# SWD_OptoIsolator.net
KiCad netlist of a schematic drawn in EAGLE
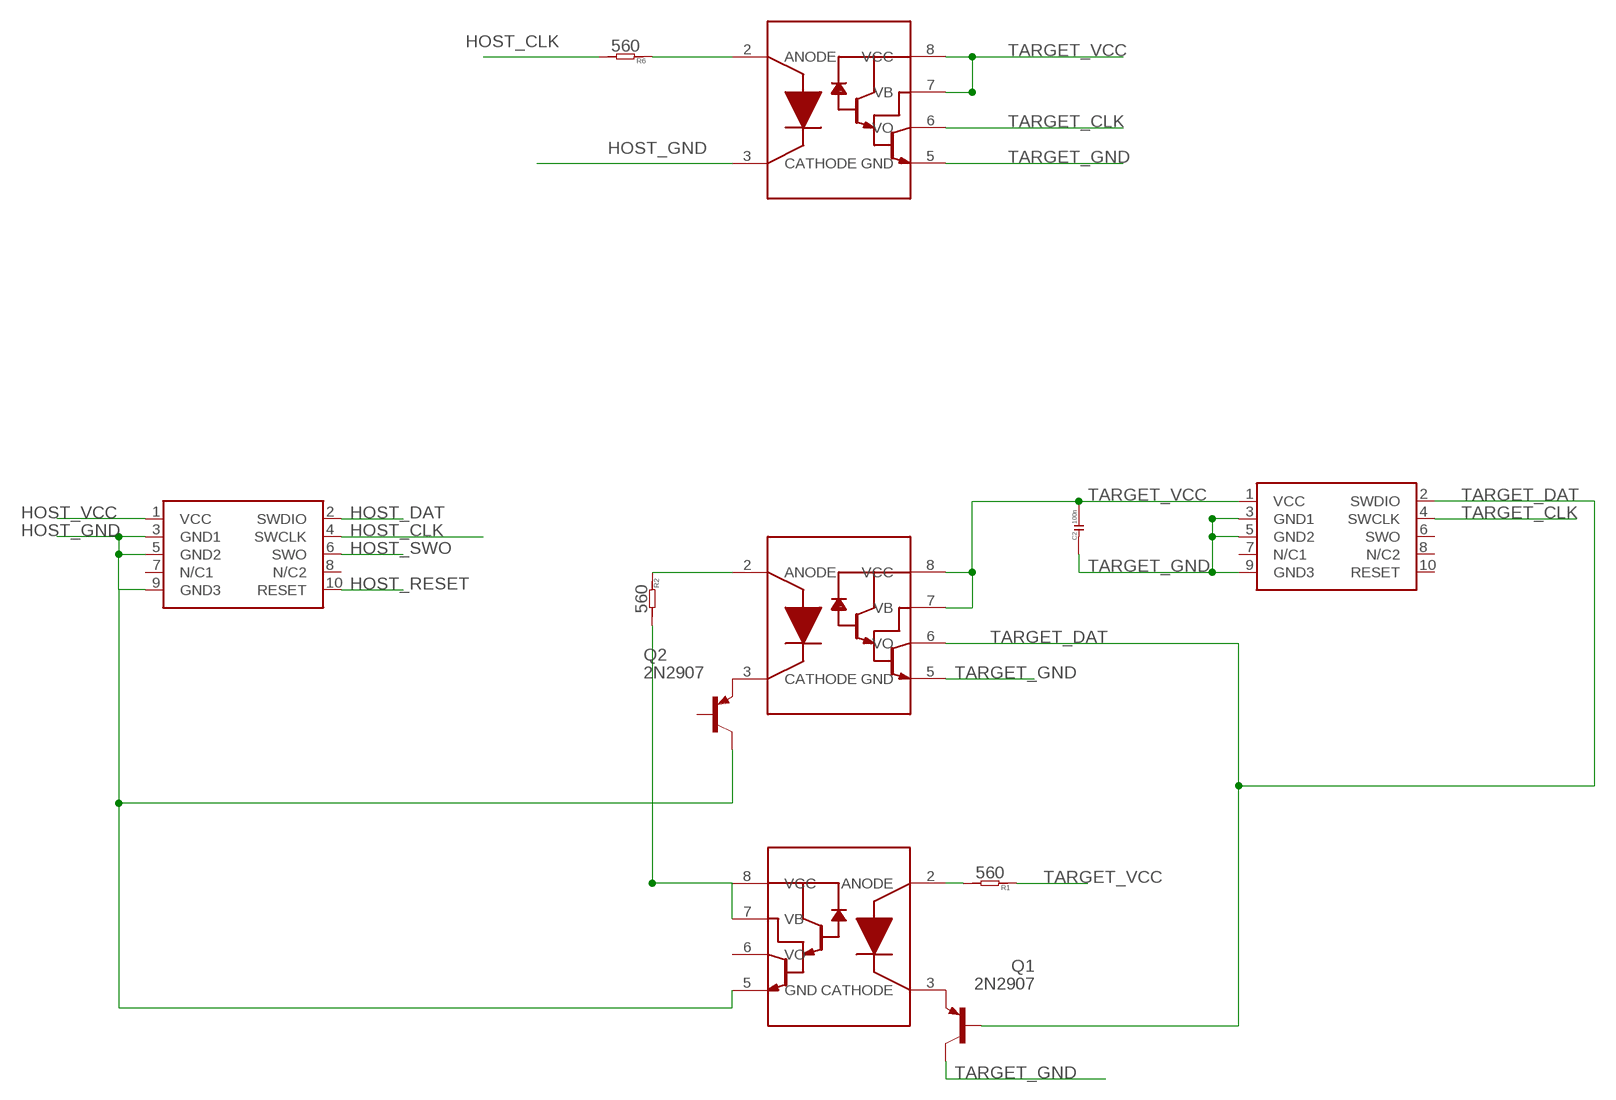
[diagram p0: schematic, sheet 1]

(export (version "E")
  (design (tool "Eeschema 10.0.6"))
  (components
    (comp (ref "C2")
      (value "100n")
      (footprint "eagle-import:C0603")
      (libsource (lib "eagle-import") (part "C-0603"))
    )
    (comp (ref "Q1")
      (value "2N2907")
      (footprint "eagle-import:TO92-EBC-OVAL")
      (libsource (lib "eagle-import") (part "2N2907"))
    )
    (comp (ref "Q2")
      (value "2N2907")
      (footprint "eagle-import:TO92-EBC-OVAL")
      (libsource (lib "eagle-import") (part "2N2907"))
    )
    (comp (ref "R1")
      (value "560")
      (footprint "eagle-import:R0603")
      (libsource (lib "eagle-import") (part "R-0603"))
    )
    (comp (ref "R2")
      (value "560")
      (footprint "eagle-import:R0603")
      (libsource (lib "eagle-import") (part "R-0603"))
    )
    (comp (ref "R6")
      (value "560")
      (footprint "eagle-import:R0603")
      (libsource (lib "eagle-import") (part "R-0603"))
    )
    (comp (ref "SWD1")
      (value "CORTEX_SWD")
      (footprint "eagle-import:M50-3600542")
      (libsource (lib "eagle-import") (part "CORTEX_SWD"))
    )
    (comp (ref "SWD2")
      (value "CORTEX_SWD")
      (footprint "eagle-import:M50-3600542")
      (libsource (lib "eagle-import") (part "CORTEX_SWD"))
    )
    (comp (ref "U$1")
      (value "6N139S")
      (footprint "eagle-import:8DIPSMD")
      (libsource (lib "eagle-import") (part "6N139S"))
    )
    (comp (ref "U$2")
      (value "6N139S")
      (footprint "eagle-import:8DIPSMD")
      (libsource (lib "eagle-import") (part "6N139S"))
    )
    (comp (ref "U$20")
      (value "6N139S")
      (footprint "eagle-import:8DIPSMD")
      (libsource (lib "eagle-import") (part "6N139S"))
    )
  )
  (nets
    (net (code "1") (name "/HOST_CLK") (class "Default")
      (node (ref "R6") (pin "2") (pinfunction "2_2") (pintype "bidirectional"))
      (node (ref "SWD1") (pin "4") (pinfunction "SWCLK_4") (pintype "bidirectional"))
    )
    (net (code "2") (name "/HOST_DAT") (class "Default")
      (node (ref "SWD1") (pin "2") (pinfunction "SWDIO_2") (pintype "bidirectional"))
    )
    (net (code "3") (name "/HOST_GND") (class "Default")
      (node (ref "Q2") (pin "C") (pinfunction "C_C") (pintype "passive"))
      (node (ref "SWD1") (pin "3") (pinfunction "GND1_3") (pintype "bidirectional"))
      (node (ref "SWD1") (pin "5") (pinfunction "GND2_5") (pintype "bidirectional"))
      (node (ref "SWD1") (pin "9") (pinfunction "GND3_9") (pintype "bidirectional"))
      (node (ref "U$1") (pin "5") (pinfunction "GND_5") (pintype "bidirectional"))
      (node (ref "U$2") (pin "3") (pinfunction "CATHODE_3") (pintype "bidirectional"))
    )
    (net (code "4") (name "/HOST_RESET") (class "Default")
      (node (ref "SWD1") (pin "10") (pinfunction "RESET_10") (pintype "bidirectional"))
    )
    (net (code "5") (name "/HOST_SWO") (class "Default")
      (node (ref "SWD1") (pin "6") (pinfunction "SWO_6") (pintype "bidirectional"))
    )
    (net (code "6") (name "/HOST_VCC") (class "Default")
      (node (ref "SWD1") (pin "1") (pinfunction "VCC_1") (pintype "bidirectional"))
    )
    (net (code "7") (name "/TARGET_CLK") (class "Default")
      (node (ref "SWD2") (pin "4") (pinfunction "SWCLK_4") (pintype "bidirectional"))
      (node (ref "U$2") (pin "6") (pinfunction "VO_6") (pintype "bidirectional"))
    )
    (net (code "8") (name "/TARGET_DAT") (class "Default")
      (node (ref "Q1") (pin "B") (pinfunction "B_B") (pintype "passive"))
      (node (ref "SWD2") (pin "2") (pinfunction "SWDIO_2") (pintype "bidirectional"))
      (node (ref "U$20") (pin "6") (pinfunction "VO_6") (pintype "bidirectional"))
    )
    (net (code "9") (name "/TARGET_GND") (class "Default")
      (node (ref "C2") (pin "1") (pinfunction "1_1") (pintype "bidirectional"))
      (node (ref "Q1") (pin "C") (pinfunction "C_C") (pintype "passive"))
      (node (ref "SWD2") (pin "3") (pinfunction "GND1_3") (pintype "bidirectional"))
      (node (ref "SWD2") (pin "5") (pinfunction "GND2_5") (pintype "bidirectional"))
      (node (ref "SWD2") (pin "9") (pinfunction "GND3_9") (pintype "bidirectional"))
      (node (ref "U$2") (pin "5") (pinfunction "GND_5") (pintype "bidirectional"))
      (node (ref "U$20") (pin "5") (pinfunction "GND_5") (pintype "bidirectional"))
    )
    (net (code "10") (name "/TARGET_VCC") (class "Default")
      (node (ref "C2") (pin "2") (pinfunction "2_2") (pintype "bidirectional"))
      (node (ref "R1") (pin "1") (pinfunction "1_1") (pintype "bidirectional"))
      (node (ref "SWD2") (pin "1") (pinfunction "VCC_1") (pintype "bidirectional"))
      (node (ref "U$2") (pin "7") (pinfunction "VB_7") (pintype "bidirectional"))
      (node (ref "U$2") (pin "8") (pinfunction "VCC_8") (pintype "bidirectional"))
      (node (ref "U$20") (pin "7") (pinfunction "VB_7") (pintype "bidirectional"))
      (node (ref "U$20") (pin "8") (pinfunction "VCC_8") (pintype "bidirectional"))
    )
    (net (code "11") (name "Net-(U$1-ANODE)") (class "Default")
      (node (ref "R1") (pin "2") (pinfunction "2_2") (pintype "bidirectional"))
      (node (ref "U$1") (pin "2") (pinfunction "ANODE_2") (pintype "bidirectional"))
    )
    (net (code "12") (name "Net-(U$1-CATHODE)") (class "Default")
      (node (ref "Q1") (pin "E") (pinfunction "E_E") (pintype "passive"))
      (node (ref "U$1") (pin "3") (pinfunction "CATHODE_3") (pintype "bidirectional"))
    )
    (net (code "13") (name "Net-(U$1-VB)") (class "Default")
      (node (ref "R2") (pin "2") (pinfunction "2_2") (pintype "bidirectional"))
      (node (ref "U$1") (pin "7") (pinfunction "VB_7") (pintype "bidirectional"))
      (node (ref "U$1") (pin "8") (pinfunction "VCC_8") (pintype "bidirectional"))
    )
    (net (code "14") (name "Net-(U$2-ANODE)") (class "Default")
      (node (ref "R6") (pin "1") (pinfunction "1_1") (pintype "bidirectional"))
      (node (ref "U$2") (pin "2") (pinfunction "ANODE_2") (pintype "bidirectional"))
    )
    (net (code "15") (name "Net-(U$20-ANODE)") (class "Default")
      (node (ref "R2") (pin "1") (pinfunction "1_1") (pintype "bidirectional"))
      (node (ref "U$20") (pin "2") (pinfunction "ANODE_2") (pintype "bidirectional"))
    )
    (net (code "16") (name "Net-(U$20-CATHODE)") (class "Default")
      (node (ref "Q2") (pin "E") (pinfunction "E_E") (pintype "passive"))
      (node (ref "U$20") (pin "3") (pinfunction "CATHODE_3") (pintype "bidirectional"))
    )
    (net (code "17") (name "unconnected-(Q2-PadB)") (class "Default")
      (node (ref "Q2") (pin "B") (pinfunction "B_B") (pintype "passive"))
    )
    (net (code "18") (name "unconnected-(SWD1-N{slash}C1-Pad7)") (class "Default")
      (node (ref "SWD1") (pin "7") (pinfunction "N/C1_7") (pintype "bidirectional"))
    )
    (net (code "19") (name "unconnected-(SWD1-N{slash}C2-Pad8)") (class "Default")
      (node (ref "SWD1") (pin "8") (pinfunction "N/C2_8") (pintype "bidirectional"))
    )
    (net (code "20") (name "unconnected-(SWD2-N{slash}C1-Pad7)") (class "Default")
      (node (ref "SWD2") (pin "7") (pinfunction "N/C1_7") (pintype "bidirectional"))
    )
    (net (code "21") (name "unconnected-(SWD2-N{slash}C2-Pad8)") (class "Default")
      (node (ref "SWD2") (pin "8") (pinfunction "N/C2_8") (pintype "bidirectional"))
    )
    (net (code "22") (name "unconnected-(SWD2-RESET-Pad10)") (class "Default")
      (node (ref "SWD2") (pin "10") (pinfunction "RESET_10") (pintype "bidirectional"))
    )
    (net (code "23") (name "unconnected-(SWD2-SWO-Pad6)") (class "Default")
      (node (ref "SWD2") (pin "6") (pinfunction "SWO_6") (pintype "bidirectional"))
    )
    (net (code "24") (name "unconnected-(U$1-VO-Pad6)") (class "Default")
      (node (ref "U$1") (pin "6") (pinfunction "VO_6") (pintype "bidirectional"))
    )
  )
)
